# center.net
KiCad netlist of a schematic drawn in EAGLE
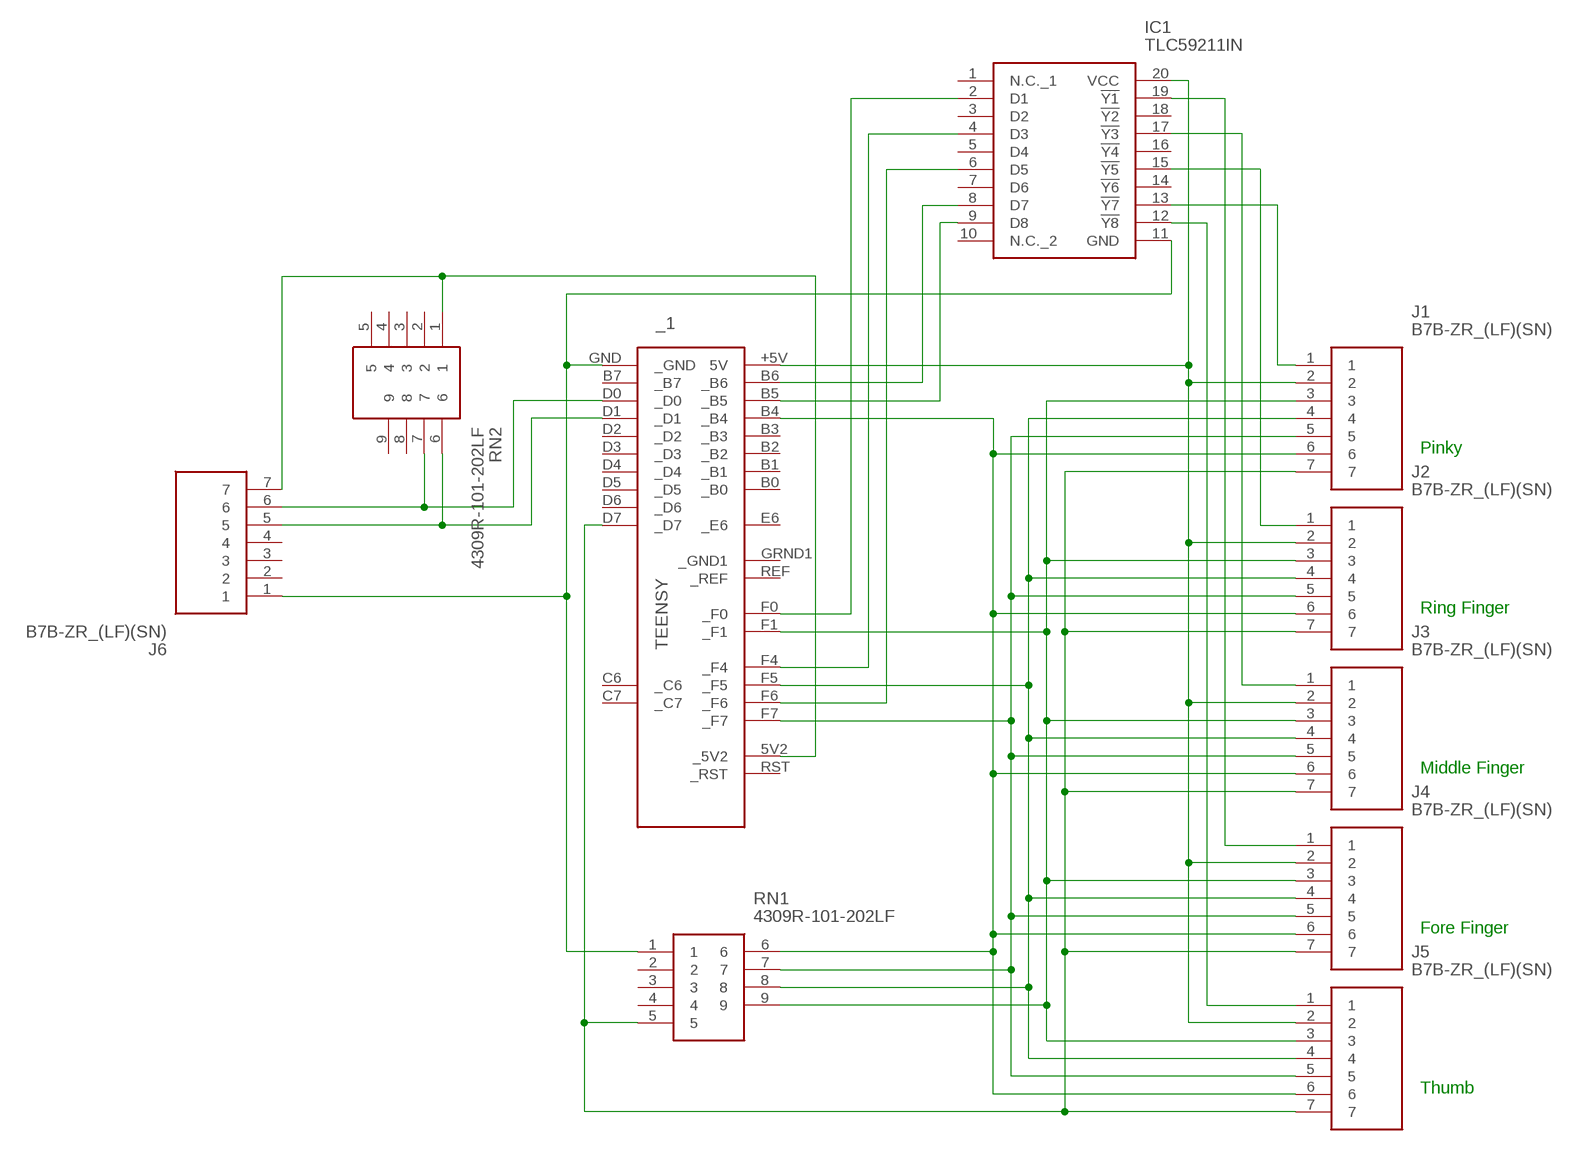
[diagram p0: schematic, sheet 1]

(export (version "E")
  (design (tool "Eeschema 10.0.6"))
  (components
    (comp (ref "IC1")
      (value "TLC59211IN")
      (footprint "eagle-import:DIP794W53P254L2540H508Q20N")
      (fields (field (name "MOUSER_PART_NUMBER") "595-TLC59211IN"))
      (libsource (lib "eagle-import") (part "TLC59211IN"))
    )
    (comp (ref "J1")
      (value "B7B-ZR_(LF)(SN)")
      (footprint "eagle-import:SHDR7W50P0X150_1X7_1200X350X45")
      (fields
        (field (name "MANUFACTURER_PART_NUMBER") "B7B-ZR (LF)(SN)")
        (field (name "RS_PART_NUMBER") "7620828")
      )
      (libsource (lib "eagle-import") (part "B7B-ZR_(LF)(SN)"))
    )
    (comp (ref "J2")
      (value "B7B-ZR_(LF)(SN)")
      (footprint "eagle-import:SHDR7W50P0X150_1X7_1200X350X45")
      (fields
        (field (name "MANUFACTURER_PART_NUMBER") "B7B-ZR (LF)(SN)")
        (field (name "RS_PART_NUMBER") "7620828")
      )
      (libsource (lib "eagle-import") (part "B7B-ZR_(LF)(SN)"))
    )
    (comp (ref "J3")
      (value "B7B-ZR_(LF)(SN)")
      (footprint "eagle-import:SHDR7W50P0X150_1X7_1200X350X45")
      (fields
        (field (name "MANUFACTURER_PART_NUMBER") "B7B-ZR (LF)(SN)")
        (field (name "RS_PART_NUMBER") "7620828")
      )
      (libsource (lib "eagle-import") (part "B7B-ZR_(LF)(SN)"))
    )
    (comp (ref "J4")
      (value "B7B-ZR_(LF)(SN)")
      (footprint "eagle-import:SHDR7W50P0X150_1X7_1200X350X45")
      (fields
        (field (name "MANUFACTURER_PART_NUMBER") "B7B-ZR (LF)(SN)")
        (field (name "RS_PART_NUMBER") "7620828")
      )
      (libsource (lib "eagle-import") (part "B7B-ZR_(LF)(SN)"))
    )
    (comp (ref "J5")
      (value "B7B-ZR_(LF)(SN)")
      (footprint "eagle-import:SHDR7W50P0X150_1X7_1200X350X45")
      (fields
        (field (name "MANUFACTURER_PART_NUMBER") "B7B-ZR (LF)(SN)")
        (field (name "RS_PART_NUMBER") "7620828")
      )
      (libsource (lib "eagle-import") (part "B7B-ZR_(LF)(SN)"))
    )
    (comp (ref "J6")
      (value "B7B-ZR_(LF)(SN)")
      (footprint "eagle-import:SHDR7W50P0X150_1X7_1200X350X45")
      (fields
        (field (name "MANUFACTURER_PART_NUMBER") "B7B-ZR (LF)(SN)")
        (field (name "RS_PART_NUMBER") "7620828")
      )
      (libsource (lib "eagle-import") (part "B7B-ZR_(LF)(SN)"))
    )
    (comp (ref "RN1")
      (value "4309R-101-202LF")
      (footprint "eagle-import:4309R-101")
      (fields (field (name "MOUSER_PART_NUMBER") "652-4309R-1LF-2K"))
      (libsource (lib "eagle-import") (part "4309R-101-202LF"))
    )
    (comp (ref "RN2")
      (value "4309R-101-202LF")
      (footprint "eagle-import:4309R-101")
      (fields (field (name "MOUSER_PART_NUMBER") "652-4309R-1LF-2K"))
      (libsource (lib "eagle-import") (part "4309R-101-202LF"))
    )
    (comp (ref "_1")
      (value "TEENSY")
      (footprint "eagle-import:TEENSY")
      (libsource (lib "eagle-import") (part "TEENSY"))
    )
  )
  (nets
    (net (code "1") (name "Net-(IC1-D1)") (class "Default")
      (node (ref "IC1") (pin "2") (pinfunction "D1_2") (pintype "bidirectional"))
      (node (ref "_1") (pin "F0") (pinfunction "_F0_F0") (pintype "bidirectional"))
    )
    (net (code "2") (name "Net-(IC1-D3)") (class "Default")
      (node (ref "IC1") (pin "4") (pinfunction "D3_4") (pintype "bidirectional"))
      (node (ref "_1") (pin "F4") (pinfunction "_F4_F4") (pintype "bidirectional"))
    )
    (net (code "3") (name "Net-(IC1-D5)") (class "Default")
      (node (ref "IC1") (pin "6") (pinfunction "D5_6") (pintype "bidirectional"))
      (node (ref "_1") (pin "F6") (pinfunction "_F6_F6") (pintype "bidirectional"))
    )
    (net (code "4") (name "Net-(IC1-D7)") (class "Default")
      (node (ref "IC1") (pin "8") (pinfunction "D7_8") (pintype "bidirectional"))
      (node (ref "_1") (pin "B6") (pinfunction "_B6_B6") (pintype "bidirectional"))
    )
    (net (code "5") (name "Net-(IC1-D8)") (class "Default")
      (node (ref "IC1") (pin "9") (pinfunction "D8_9") (pintype "bidirectional"))
      (node (ref "_1") (pin "B5") (pinfunction "_B5_B5") (pintype "bidirectional"))
    )
    (net (code "6") (name "Net-(IC1-GND)") (class "Default")
      (node (ref "IC1") (pin "11") (pinfunction "GND_11") (pintype "bidirectional"))
      (node (ref "J6") (pin "1") (pinfunction "1_1") (pintype "bidirectional"))
      (node (ref "RN1") (pin "1") (pinfunction "1_1") (pintype "bidirectional"))
      (node (ref "_1") (pin "GND") (pinfunction "_GND_GND") (pintype "bidirectional"))
    )
    (net (code "7") (name "Net-(IC1-VCC)") (class "Default")
      (node (ref "IC1") (pin "20") (pinfunction "VCC_20") (pintype "bidirectional"))
      (node (ref "J1") (pin "2") (pinfunction "2_2") (pintype "bidirectional"))
      (node (ref "J2") (pin "2") (pinfunction "2_2") (pintype "bidirectional"))
      (node (ref "J3") (pin "2") (pinfunction "2_2") (pintype "bidirectional"))
      (node (ref "J4") (pin "2") (pinfunction "2_2") (pintype "bidirectional"))
      (node (ref "J5") (pin "2") (pinfunction "2_2") (pintype "bidirectional"))
      (node (ref "_1") (pin "+5V") (pinfunction "5V_+5V") (pintype "bidirectional"))
    )
    (net (code "8") (name "Net-(IC1-~{Y1})") (class "Default")
      (node (ref "IC1") (pin "19") (pinfunction "~{Y1}_19") (pintype "bidirectional"))
      (node (ref "J4") (pin "1") (pinfunction "1_1") (pintype "bidirectional"))
    )
    (net (code "9") (name "Net-(IC1-~{Y3})") (class "Default")
      (node (ref "IC1") (pin "17") (pinfunction "~{Y3}_17") (pintype "bidirectional"))
      (node (ref "J3") (pin "1") (pinfunction "1_1") (pintype "bidirectional"))
    )
    (net (code "10") (name "Net-(IC1-~{Y5})") (class "Default")
      (node (ref "IC1") (pin "15") (pinfunction "~{Y5}_15") (pintype "bidirectional"))
      (node (ref "J2") (pin "1") (pinfunction "1_1") (pintype "bidirectional"))
    )
    (net (code "11") (name "Net-(IC1-~{Y7})") (class "Default")
      (node (ref "IC1") (pin "13") (pinfunction "~{Y7}_13") (pintype "bidirectional"))
      (node (ref "J1") (pin "1") (pinfunction "1_1") (pintype "bidirectional"))
    )
    (net (code "12") (name "Net-(IC1-~{Y8})") (class "Default")
      (node (ref "IC1") (pin "12") (pinfunction "~{Y8}_12") (pintype "bidirectional"))
      (node (ref "J5") (pin "1") (pinfunction "1_1") (pintype "bidirectional"))
    )
    (net (code "13") (name "Net-(_1-_5V2)") (class "Default")
      (node (ref "J6") (pin "7") (pinfunction "7_7") (pintype "bidirectional"))
      (node (ref "RN2") (pin "1") (pinfunction "1_1") (pintype "bidirectional"))
      (node (ref "_1") (pin "5V2") (pinfunction "_5V2_5V2") (pintype "bidirectional"))
    )
    (net (code "14") (name "Net-(_1-_B4)") (class "Default")
      (node (ref "J1") (pin "6") (pinfunction "6_6") (pintype "bidirectional"))
      (node (ref "J2") (pin "6") (pinfunction "6_6") (pintype "bidirectional"))
      (node (ref "J3") (pin "6") (pinfunction "6_6") (pintype "bidirectional"))
      (node (ref "J4") (pin "6") (pinfunction "6_6") (pintype "bidirectional"))
      (node (ref "J5") (pin "6") (pinfunction "6_6") (pintype "bidirectional"))
      (node (ref "RN1") (pin "6") (pinfunction "6_6") (pintype "bidirectional"))
      (node (ref "_1") (pin "B4") (pinfunction "_B4_B4") (pintype "bidirectional"))
    )
    (net (code "15") (name "Net-(_1-_D0)") (class "Default")
      (node (ref "J6") (pin "6") (pinfunction "6_6") (pintype "bidirectional"))
      (node (ref "RN2") (pin "7") (pinfunction "7_7") (pintype "bidirectional"))
      (node (ref "_1") (pin "D0") (pinfunction "_D0_D0") (pintype "bidirectional"))
    )
    (net (code "16") (name "Net-(_1-_D1)") (class "Default")
      (node (ref "J6") (pin "5") (pinfunction "5_5") (pintype "bidirectional"))
      (node (ref "RN2") (pin "6") (pinfunction "6_6") (pintype "bidirectional"))
      (node (ref "_1") (pin "D1") (pinfunction "_D1_D1") (pintype "bidirectional"))
    )
    (net (code "17") (name "Net-(_1-_D7)") (class "Default")
      (node (ref "J1") (pin "7") (pinfunction "7_7") (pintype "bidirectional"))
      (node (ref "J2") (pin "7") (pinfunction "7_7") (pintype "bidirectional"))
      (node (ref "J3") (pin "7") (pinfunction "7_7") (pintype "bidirectional"))
      (node (ref "J4") (pin "7") (pinfunction "7_7") (pintype "bidirectional"))
      (node (ref "J5") (pin "7") (pinfunction "7_7") (pintype "bidirectional"))
      (node (ref "RN1") (pin "5") (pinfunction "5_5") (pintype "bidirectional"))
      (node (ref "_1") (pin "D7") (pinfunction "_D7_D7") (pintype "bidirectional"))
    )
    (net (code "18") (name "Net-(_1-_F1)") (class "Default")
      (node (ref "J1") (pin "3") (pinfunction "3_3") (pintype "bidirectional"))
      (node (ref "J2") (pin "3") (pinfunction "3_3") (pintype "bidirectional"))
      (node (ref "J3") (pin "3") (pinfunction "3_3") (pintype "bidirectional"))
      (node (ref "J4") (pin "3") (pinfunction "3_3") (pintype "bidirectional"))
      (node (ref "J5") (pin "3") (pinfunction "3_3") (pintype "bidirectional"))
      (node (ref "RN1") (pin "9") (pinfunction "9_9") (pintype "bidirectional"))
      (node (ref "_1") (pin "F1") (pinfunction "_F1_F1") (pintype "bidirectional"))
    )
    (net (code "19") (name "Net-(_1-_F5)") (class "Default")
      (node (ref "J1") (pin "4") (pinfunction "4_4") (pintype "bidirectional"))
      (node (ref "J2") (pin "4") (pinfunction "4_4") (pintype "bidirectional"))
      (node (ref "J3") (pin "4") (pinfunction "4_4") (pintype "bidirectional"))
      (node (ref "J4") (pin "4") (pinfunction "4_4") (pintype "bidirectional"))
      (node (ref "J5") (pin "4") (pinfunction "4_4") (pintype "bidirectional"))
      (node (ref "RN1") (pin "8") (pinfunction "8_8") (pintype "bidirectional"))
      (node (ref "_1") (pin "F5") (pinfunction "_F5_F5") (pintype "bidirectional"))
    )
    (net (code "20") (name "Net-(_1-_F7)") (class "Default")
      (node (ref "J1") (pin "5") (pinfunction "5_5") (pintype "bidirectional"))
      (node (ref "J2") (pin "5") (pinfunction "5_5") (pintype "bidirectional"))
      (node (ref "J3") (pin "5") (pinfunction "5_5") (pintype "bidirectional"))
      (node (ref "J4") (pin "5") (pinfunction "5_5") (pintype "bidirectional"))
      (node (ref "J5") (pin "5") (pinfunction "5_5") (pintype "bidirectional"))
      (node (ref "RN1") (pin "7") (pinfunction "7_7") (pintype "bidirectional"))
      (node (ref "_1") (pin "F7") (pinfunction "_F7_F7") (pintype "bidirectional"))
    )
    (net (code "21") (name "unconnected-(IC1-D2-Pad3)") (class "Default")
      (node (ref "IC1") (pin "3") (pinfunction "D2_3") (pintype "bidirectional"))
    )
    (net (code "22") (name "unconnected-(IC1-D4-Pad5)") (class "Default")
      (node (ref "IC1") (pin "5") (pinfunction "D4_5") (pintype "bidirectional"))
    )
    (net (code "23") (name "unconnected-(IC1-D6-Pad7)") (class "Default")
      (node (ref "IC1") (pin "7") (pinfunction "D6_7") (pintype "bidirectional"))
    )
    (net (code "24") (name "unconnected-(IC1-N.C._1-Pad1)") (class "Default")
      (node (ref "IC1") (pin "1") (pinfunction "N.C._1_1") (pintype "bidirectional"))
    )
    (net (code "25") (name "unconnected-(IC1-N.C._2-Pad10)") (class "Default")
      (node (ref "IC1") (pin "10") (pinfunction "N.C._2_10") (pintype "bidirectional"))
    )
    (net (code "26") (name "unconnected-(IC1-~{Y2}-Pad18)") (class "Default")
      (node (ref "IC1") (pin "18") (pinfunction "~{Y2}_18") (pintype "bidirectional"))
    )
    (net (code "27") (name "unconnected-(IC1-~{Y4}-Pad16)") (class "Default")
      (node (ref "IC1") (pin "16") (pinfunction "~{Y4}_16") (pintype "bidirectional"))
    )
    (net (code "28") (name "unconnected-(IC1-~{Y6}-Pad14)") (class "Default")
      (node (ref "IC1") (pin "14") (pinfunction "~{Y6}_14") (pintype "bidirectional"))
    )
    (net (code "29") (name "unconnected-(J6-Pad2)") (class "Default")
      (node (ref "J6") (pin "2") (pinfunction "2_2") (pintype "bidirectional"))
    )
    (net (code "30") (name "unconnected-(J6-Pad3)") (class "Default")
      (node (ref "J6") (pin "3") (pinfunction "3_3") (pintype "bidirectional"))
    )
    (net (code "31") (name "unconnected-(J6-Pad4)") (class "Default")
      (node (ref "J6") (pin "4") (pinfunction "4_4") (pintype "bidirectional"))
    )
    (net (code "32") (name "unconnected-(RN1-Pad2)") (class "Default")
      (node (ref "RN1") (pin "2") (pinfunction "2_2") (pintype "bidirectional"))
    )
    (net (code "33") (name "unconnected-(RN1-Pad3)") (class "Default")
      (node (ref "RN1") (pin "3") (pinfunction "3_3") (pintype "bidirectional"))
    )
    (net (code "34") (name "unconnected-(RN1-Pad4)") (class "Default")
      (node (ref "RN1") (pin "4") (pinfunction "4_4") (pintype "bidirectional"))
    )
    (net (code "35") (name "unconnected-(RN2-Pad2)") (class "Default")
      (node (ref "RN2") (pin "2") (pinfunction "2_2") (pintype "bidirectional"))
    )
    (net (code "36") (name "unconnected-(RN2-Pad3)") (class "Default")
      (node (ref "RN2") (pin "3") (pinfunction "3_3") (pintype "bidirectional"))
    )
    (net (code "37") (name "unconnected-(RN2-Pad4)") (class "Default")
      (node (ref "RN2") (pin "4") (pinfunction "4_4") (pintype "bidirectional"))
    )
    (net (code "38") (name "unconnected-(RN2-Pad5)") (class "Default")
      (node (ref "RN2") (pin "5") (pinfunction "5_5") (pintype "bidirectional"))
    )
    (net (code "39") (name "unconnected-(RN2-Pad8)") (class "Default")
      (node (ref "RN2") (pin "8") (pinfunction "8_8") (pintype "bidirectional"))
    )
    (net (code "40") (name "unconnected-(RN2-Pad9)") (class "Default")
      (node (ref "RN2") (pin "9") (pinfunction "9_9") (pintype "bidirectional"))
    )
    (net (code "41") (name "unconnected-(_1-_B0-PadB0)") (class "Default")
      (node (ref "_1") (pin "B0") (pinfunction "_B0_B0") (pintype "bidirectional"))
    )
    (net (code "42") (name "unconnected-(_1-_B1-PadB1)") (class "Default")
      (node (ref "_1") (pin "B1") (pinfunction "_B1_B1") (pintype "bidirectional"))
    )
    (net (code "43") (name "unconnected-(_1-_B2-PadB2)") (class "Default")
      (node (ref "_1") (pin "B2") (pinfunction "_B2_B2") (pintype "bidirectional"))
    )
    (net (code "44") (name "unconnected-(_1-_B3-PadB3)") (class "Default")
      (node (ref "_1") (pin "B3") (pinfunction "_B3_B3") (pintype "bidirectional"))
    )
    (net (code "45") (name "unconnected-(_1-_B7-PadB7)") (class "Default")
      (node (ref "_1") (pin "B7") (pinfunction "_B7_B7") (pintype "bidirectional"))
    )
    (net (code "46") (name "unconnected-(_1-_C6-PadC6)") (class "Default")
      (node (ref "_1") (pin "C6") (pinfunction "_C6_C6") (pintype "bidirectional"))
    )
    (net (code "47") (name "unconnected-(_1-_C7-PadC7)") (class "Default")
      (node (ref "_1") (pin "C7") (pinfunction "_C7_C7") (pintype "bidirectional"))
    )
    (net (code "48") (name "unconnected-(_1-_D2-PadD2)") (class "Default")
      (node (ref "_1") (pin "D2") (pinfunction "_D2_D2") (pintype "bidirectional"))
    )
    (net (code "49") (name "unconnected-(_1-_D3-PadD3)") (class "Default")
      (node (ref "_1") (pin "D3") (pinfunction "_D3_D3") (pintype "bidirectional"))
    )
    (net (code "50") (name "unconnected-(_1-_D4-PadD4)") (class "Default")
      (node (ref "_1") (pin "D4") (pinfunction "_D4_D4") (pintype "bidirectional"))
    )
    (net (code "51") (name "unconnected-(_1-_D5-PadD5)") (class "Default")
      (node (ref "_1") (pin "D5") (pinfunction "_D5_D5") (pintype "bidirectional"))
    )
    (net (code "52") (name "unconnected-(_1-_D6-PadD6)") (class "Default")
      (node (ref "_1") (pin "D6") (pinfunction "_D6_D6") (pintype "bidirectional"))
    )
    (net (code "53") (name "unconnected-(_1-_E6-PadE6)") (class "Default")
      (node (ref "_1") (pin "E6") (pinfunction "_E6_E6") (pintype "bidirectional"))
    )
    (net (code "54") (name "unconnected-(_1-_GND1-PadGRND1)") (class "Default")
      (node (ref "_1") (pin "GRND1") (pinfunction "_GND1_GRND1") (pintype "bidirectional"))
    )
    (net (code "55") (name "unconnected-(_1-_REF-PadREF)") (class "Default")
      (node (ref "_1") (pin "REF") (pinfunction "_REF_REF") (pintype "bidirectional"))
    )
    (net (code "56") (name "unconnected-(_1-_RST-PadRST)") (class "Default")
      (node (ref "_1") (pin "RST") (pinfunction "_RST_RST") (pintype "bidirectional"))
    )
  )
)
